# Shield_GRBL_V2.net
KiCad netlist of a schematic drawn in EAGLE
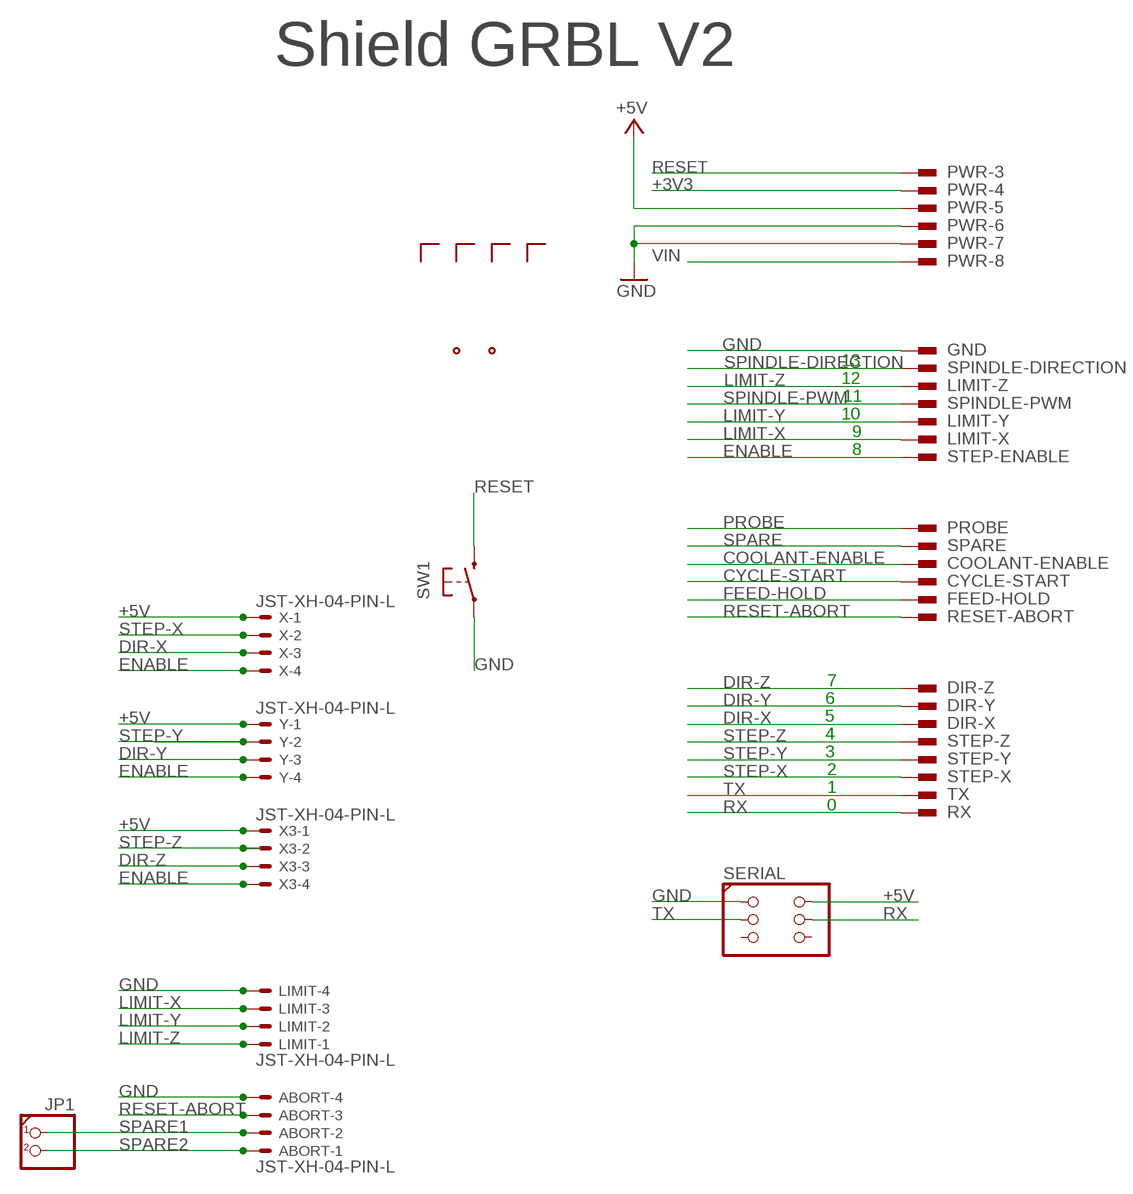
[diagram p0: schematic, sheet 1]

(export (version "E")
  (design (tool "Eeschema 10.0.6"))
  (components
    (comp (ref "ABORT")
      (value "JST-XH-04-PIN-L")
      (footprint "eagle-import:JST-XH-04-PACKAGE-LONG-PAD")
      (libsource (lib "eagle-import") (part "JST-XH-04-PIN-L"))
    )
    (comp (ref "COOLANT-ENABLE")
      (value "PINHD-1X1")
      (footprint "eagle-import:1X01")
      (fields (field (name "MF") "TYCO ELECTRONICS") (field (name "MPN") "62221-1"))
      (libsource (lib "eagle-import") (part "PINHD-1X1"))
    )
    (comp (ref "CYCLE-START")
      (value "PINHD-1X1")
      (footprint "eagle-import:1X01")
      (fields (field (name "MF") "TYCO ELECTRONICS") (field (name "MPN") "62221-1"))
      (libsource (lib "eagle-import") (part "PINHD-1X1"))
    )
    (comp (ref "DIR-X")
      (value "PINHD-1X1")
      (footprint "eagle-import:1X01")
      (fields (field (name "MF") "TYCO ELECTRONICS") (field (name "MPN") "62221-1"))
      (libsource (lib "eagle-import") (part "PINHD-1X1"))
    )
    (comp (ref "DIR-Y")
      (value "PINHD-1X1")
      (footprint "eagle-import:1X01")
      (fields (field (name "MF") "TYCO ELECTRONICS") (field (name "MPN") "62221-1"))
      (libsource (lib "eagle-import") (part "PINHD-1X1"))
    )
    (comp (ref "DIR-Z")
      (value "PINHD-1X1")
      (footprint "eagle-import:1X01")
      (fields (field (name "MF") "TYCO ELECTRONICS") (field (name "MPN") "62221-1"))
      (libsource (lib "eagle-import") (part "PINHD-1X1"))
    )
    (comp (ref "FEED-HOLD")
      (value "PINHD-1X1")
      (footprint "eagle-import:1X01")
      (fields (field (name "MF") "TYCO ELECTRONICS") (field (name "MPN") "62221-1"))
      (libsource (lib "eagle-import") (part "PINHD-1X1"))
    )
    (comp (ref "GND")
      (value "PINHD-1X1")
      (footprint "eagle-import:1X01")
      (fields (field (name "MF") "TYCO ELECTRONICS") (field (name "MPN") "62221-1"))
      (libsource (lib "eagle-import") (part "PINHD-1X1"))
    )
    (comp (ref "JP1")
      (value "PINHD-1X2")
      (footprint "eagle-import:1X02")
      (libsource (lib "eagle-import") (part "PINHD-1X2"))
    )
    (comp (ref "LIMIT")
      (value "JST-XH-04-PIN-L")
      (footprint "eagle-import:JST-XH-04-PACKAGE-LONG-PAD")
      (libsource (lib "eagle-import") (part "JST-XH-04-PIN-L"))
    )
    (comp (ref "LIMIT-X")
      (value "PINHD-1X1")
      (footprint "eagle-import:1X01")
      (fields (field (name "MF") "TYCO ELECTRONICS") (field (name "MPN") "62221-1"))
      (libsource (lib "eagle-import") (part "PINHD-1X1"))
    )
    (comp (ref "LIMIT-Y")
      (value "PINHD-1X1")
      (footprint "eagle-import:1X01")
      (fields (field (name "MF") "TYCO ELECTRONICS") (field (name "MPN") "62221-1"))
      (libsource (lib "eagle-import") (part "PINHD-1X1"))
    )
    (comp (ref "LIMIT-Z")
      (value "PINHD-1X1")
      (footprint "eagle-import:1X01")
      (fields (field (name "MF") "TYCO ELECTRONICS") (field (name "MPN") "62221-1"))
      (libsource (lib "eagle-import") (part "PINHD-1X1"))
    )
    (comp (ref "PROBE")
      (value "PINHD-1X1")
      (footprint "eagle-import:1X01")
      (fields (field (name "MF") "TYCO ELECTRONICS") (field (name "MPN") "62221-1"))
      (libsource (lib "eagle-import") (part "PINHD-1X1"))
    )
    (comp (ref "PWR-3")
      (value "PINHD-1X1")
      (footprint "eagle-import:1X01")
      (fields (field (name "MF") "TYCO ELECTRONICS") (field (name "MPN") "62221-1"))
      (libsource (lib "eagle-import") (part "PINHD-1X1"))
    )
    (comp (ref "PWR-4")
      (value "PINHD-1X1")
      (footprint "eagle-import:1X01")
      (fields (field (name "MF") "TYCO ELECTRONICS") (field (name "MPN") "62221-1"))
      (libsource (lib "eagle-import") (part "PINHD-1X1"))
    )
    (comp (ref "PWR-5")
      (value "PINHD-1X1")
      (footprint "eagle-import:1X01")
      (fields (field (name "MF") "TYCO ELECTRONICS") (field (name "MPN") "62221-1"))
      (libsource (lib "eagle-import") (part "PINHD-1X1"))
    )
    (comp (ref "PWR-6")
      (value "PINHD-1X1")
      (footprint "eagle-import:1X01")
      (fields (field (name "MF") "TYCO ELECTRONICS") (field (name "MPN") "62221-1"))
      (libsource (lib "eagle-import") (part "PINHD-1X1"))
    )
    (comp (ref "PWR-7")
      (value "PINHD-1X1")
      (footprint "eagle-import:1X01")
      (fields (field (name "MF") "TYCO ELECTRONICS") (field (name "MPN") "62221-1"))
      (libsource (lib "eagle-import") (part "PINHD-1X1"))
    )
    (comp (ref "PWR-8")
      (value "PINHD-1X1")
      (footprint "eagle-import:1X01")
      (fields (field (name "MF") "TYCO ELECTRONICS") (field (name "MPN") "62221-1"))
      (libsource (lib "eagle-import") (part "PINHD-1X1"))
    )
    (comp (ref "RESET-ABORT")
      (value "PINHD-1X1")
      (footprint "eagle-import:1X01")
      (fields (field (name "MF") "TYCO ELECTRONICS") (field (name "MPN") "62221-1"))
      (libsource (lib "eagle-import") (part "PINHD-1X1"))
    )
    (comp (ref "RX")
      (value "PINHD-1X1")
      (footprint "eagle-import:1X01")
      (fields (field (name "MF") "TYCO ELECTRONICS") (field (name "MPN") "62221-1"))
      (libsource (lib "eagle-import") (part "PINHD-1X1"))
    )
    (comp (ref "SERIAL")
      (value "3x2 M")
      (footprint "eagle-import:2X03S")
      (libsource (lib "eagle-import") (part "PINHD-2X3S"))
    )
    (comp (ref "SPARE")
      (value "PINHD-1X1")
      (footprint "eagle-import:1X01")
      (fields (field (name "MF") "TYCO ELECTRONICS") (field (name "MPN") "62221-1"))
      (libsource (lib "eagle-import") (part "PINHD-1X1"))
    )
    (comp (ref "SPINDLE-DIRECTION")
      (value "PINHD-1X1")
      (footprint "eagle-import:1X01")
      (fields (field (name "MF") "TYCO ELECTRONICS") (field (name "MPN") "62221-1"))
      (libsource (lib "eagle-import") (part "PINHD-1X1"))
    )
    (comp (ref "SPINDLE-PWM")
      (value "PINHD-1X1")
      (footprint "eagle-import:1X01")
      (fields (field (name "MF") "TYCO ELECTRONICS") (field (name "MPN") "62221-1"))
      (libsource (lib "eagle-import") (part "PINHD-1X1"))
    )
    (comp (ref "STEP-ENABLE")
      (value "PINHD-1X1")
      (footprint "eagle-import:1X01")
      (fields (field (name "MF") "TYCO ELECTRONICS") (field (name "MPN") "62221-1"))
      (libsource (lib "eagle-import") (part "PINHD-1X1"))
    )
    (comp (ref "STEP-X")
      (value "PINHD-1X1")
      (footprint "eagle-import:1X01")
      (fields (field (name "MF") "TYCO ELECTRONICS") (field (name "MPN") "62221-1"))
      (libsource (lib "eagle-import") (part "PINHD-1X1"))
    )
    (comp (ref "STEP-Y")
      (value "PINHD-1X1")
      (footprint "eagle-import:1X01")
      (fields (field (name "MF") "TYCO ELECTRONICS") (field (name "MPN") "62221-1"))
      (libsource (lib "eagle-import") (part "PINHD-1X1"))
    )
    (comp (ref "STEP-Z")
      (value "PINHD-1X1")
      (footprint "eagle-import:1X01")
      (fields (field (name "MF") "TYCO ELECTRONICS") (field (name "MPN") "62221-1"))
      (libsource (lib "eagle-import") (part "PINHD-1X1"))
    )
    (comp (ref "SW1")
      (value "SWITCH1X2")
      (footprint "eagle-import:SW8X4-SMD")
      (libsource (lib "eagle-import") (part "SWITCH1X2"))
    )
    (comp (ref "TX")
      (value "PINHD-1X1")
      (footprint "eagle-import:1X01")
      (fields (field (name "MF") "TYCO ELECTRONICS") (field (name "MPN") "62221-1"))
      (libsource (lib "eagle-import") (part "PINHD-1X1"))
    )
    (comp (ref "U$1")
      (value "MARKERDUAL-60")
      (footprint "eagle-import:MARKER60")
      (libsource (lib "eagle-import") (part "MARKERDUAL-60"))
    )
    (comp (ref "U$2")
      (value "MARKER")
      (footprint "eagle-import:MARKER")
      (libsource (lib "eagle-import") (part "MARKER"))
    )
    (comp (ref "U$3")
      (value "MARKER")
      (footprint "eagle-import:MARKER")
      (libsource (lib "eagle-import") (part "MARKER"))
    )
    (comp (ref "U$4")
      (value "MARKER")
      (footprint "eagle-import:MARKER")
      (libsource (lib "eagle-import") (part "MARKER"))
    )
    (comp (ref "U$5")
      (value "MARKER")
      (footprint "eagle-import:MARKER")
      (libsource (lib "eagle-import") (part "MARKER"))
    )
    (comp (ref "X")
      (value "JST-XH-04-PIN-L")
      (footprint "eagle-import:JST-XH-04-PACKAGE-LONG-PAD")
      (libsource (lib "eagle-import") (part "JST-XH-04-PIN-L"))
    )
    (comp (ref "X3")
      (value "JST-XH-04-PIN-L")
      (footprint "eagle-import:JST-XH-04-PACKAGE-LONG-PAD")
      (libsource (lib "eagle-import") (part "JST-XH-04-PIN-L"))
    )
    (comp (ref "Y")
      (value "JST-XH-04-PIN-L")
      (footprint "eagle-import:JST-XH-04-PACKAGE-LONG-PAD")
      (libsource (lib "eagle-import") (part "JST-XH-04-PIN-L"))
    )
  )
  (nets
    (net (code "1") (name "+5V") (class "Default")
      (node (ref "PWR-5") (pin "1") (pinfunction "1_1") (pintype "passive"))
      (node (ref "SERIAL") (pin "2") (pinfunction "2_2") (pintype "passive"))
      (node (ref "X") (pin "1") (pinfunction "S_1") (pintype "passive"))
      (node (ref "X3") (pin "1") (pinfunction "S_1") (pintype "passive"))
      (node (ref "Y") (pin "1") (pinfunction "S_1") (pintype "passive"))
    )
    (net (code "2") (name "/+3V3") (class "Default")
      (node (ref "PWR-4") (pin "1") (pinfunction "1_1") (pintype "passive"))
    )
    (net (code "3") (name "/COOLANT-ENABLE") (class "Default")
      (node (ref "COOLANT-ENABLE") (pin "1") (pinfunction "1_1") (pintype "passive"))
    )
    (net (code "4") (name "/CYCLE-START") (class "Default")
      (node (ref "CYCLE-START") (pin "1") (pinfunction "1_1") (pintype "passive"))
    )
    (net (code "5") (name "/DIR-X") (class "Default")
      (node (ref "DIR-X") (pin "1") (pinfunction "1_1") (pintype "passive"))
      (node (ref "X") (pin "3") (pinfunction "S_3") (pintype "passive"))
    )
    (net (code "6") (name "/DIR-Y") (class "Default")
      (node (ref "DIR-Y") (pin "1") (pinfunction "1_1") (pintype "passive"))
      (node (ref "Y") (pin "3") (pinfunction "S_3") (pintype "passive"))
    )
    (net (code "7") (name "/DIR-Z") (class "Default")
      (node (ref "DIR-Z") (pin "1") (pinfunction "1_1") (pintype "passive"))
      (node (ref "X3") (pin "3") (pinfunction "S_3") (pintype "passive"))
    )
    (net (code "8") (name "/ENABLE") (class "Default")
      (node (ref "STEP-ENABLE") (pin "1") (pinfunction "1_1") (pintype "passive"))
      (node (ref "X") (pin "4") (pinfunction "S_4") (pintype "passive"))
      (node (ref "X3") (pin "4") (pinfunction "S_4") (pintype "passive"))
      (node (ref "Y") (pin "4") (pinfunction "S_4") (pintype "passive"))
    )
    (net (code "9") (name "/FEED-HOLD") (class "Default")
      (node (ref "FEED-HOLD") (pin "1") (pinfunction "1_1") (pintype "passive"))
    )
    (net (code "10") (name "/LIMIT-X") (class "Default")
      (node (ref "LIMIT") (pin "3") (pinfunction "S_3") (pintype "passive"))
      (node (ref "LIMIT-X") (pin "1") (pinfunction "1_1") (pintype "passive"))
    )
    (net (code "11") (name "/LIMIT-Y") (class "Default")
      (node (ref "LIMIT") (pin "2") (pinfunction "S_2") (pintype "passive"))
      (node (ref "LIMIT-Y") (pin "1") (pinfunction "1_1") (pintype "passive"))
    )
    (net (code "12") (name "/LIMIT-Z") (class "Default")
      (node (ref "LIMIT") (pin "1") (pinfunction "S_1") (pintype "passive"))
      (node (ref "LIMIT-Z") (pin "1") (pinfunction "1_1") (pintype "passive"))
    )
    (net (code "13") (name "/PROBE") (class "Default")
      (node (ref "PROBE") (pin "1") (pinfunction "1_1") (pintype "passive"))
    )
    (net (code "14") (name "/RESET") (class "Default")
      (node (ref "PWR-3") (pin "1") (pinfunction "1_1") (pintype "passive"))
      (node (ref "SW1") (pin "2") (pinfunction "S_2") (pintype "passive"))
    )
    (net (code "15") (name "/RESET-ABORT") (class "Default")
      (node (ref "ABORT") (pin "3") (pinfunction "S_3") (pintype "passive"))
      (node (ref "RESET-ABORT") (pin "1") (pinfunction "1_1") (pintype "passive"))
    )
    (net (code "16") (name "/RX") (class "Default")
      (node (ref "RX") (pin "1") (pinfunction "1_1") (pintype "passive"))
      (node (ref "SERIAL") (pin "4") (pinfunction "4_4") (pintype "passive"))
    )
    (net (code "17") (name "/SPARE") (class "Default")
      (node (ref "SPARE") (pin "1") (pinfunction "1_1") (pintype "passive"))
    )
    (net (code "18") (name "/SPARE1") (class "Default")
      (node (ref "ABORT") (pin "2") (pinfunction "S_2") (pintype "passive"))
      (node (ref "JP1") (pin "1") (pinfunction "1_1") (pintype "passive"))
    )
    (net (code "19") (name "/SPARE2") (class "Default")
      (node (ref "ABORT") (pin "1") (pinfunction "S_1") (pintype "passive"))
      (node (ref "JP1") (pin "2") (pinfunction "2_2") (pintype "passive"))
    )
    (net (code "20") (name "/SPINDLE-DIRECTION") (class "Default")
      (node (ref "SPINDLE-DIRECTION") (pin "1") (pinfunction "1_1") (pintype "passive"))
    )
    (net (code "21") (name "/SPINDLE-PWM") (class "Default")
      (node (ref "SPINDLE-PWM") (pin "1") (pinfunction "1_1") (pintype "passive"))
    )
    (net (code "22") (name "/STEP-X") (class "Default")
      (node (ref "STEP-X") (pin "1") (pinfunction "1_1") (pintype "passive"))
      (node (ref "X") (pin "2") (pinfunction "S_2") (pintype "passive"))
    )
    (net (code "23") (name "/STEP-Y") (class "Default")
      (node (ref "STEP-Y") (pin "1") (pinfunction "1_1") (pintype "passive"))
      (node (ref "Y") (pin "2") (pinfunction "S_2") (pintype "passive"))
    )
    (net (code "24") (name "/STEP-Z") (class "Default")
      (node (ref "STEP-Z") (pin "1") (pinfunction "1_1") (pintype "passive"))
      (node (ref "X3") (pin "2") (pinfunction "S_2") (pintype "passive"))
    )
    (net (code "25") (name "/TX") (class "Default")
      (node (ref "SERIAL") (pin "3") (pinfunction "3_3") (pintype "passive"))
      (node (ref "TX") (pin "1") (pinfunction "1_1") (pintype "passive"))
    )
    (net (code "26") (name "/VIN") (class "Default")
      (node (ref "PWR-8") (pin "1") (pinfunction "1_1") (pintype "passive"))
    )
    (net (code "27") (name "GND") (class "Default")
      (node (ref "ABORT") (pin "4") (pinfunction "S_4") (pintype "passive"))
      (node (ref "GND") (pin "1") (pinfunction "1_1") (pintype "passive"))
      (node (ref "LIMIT") (pin "4") (pinfunction "S_4") (pintype "passive"))
      (node (ref "PWR-6") (pin "1") (pinfunction "1_1") (pintype "passive"))
      (node (ref "PWR-7") (pin "1") (pinfunction "1_1") (pintype "passive"))
      (node (ref "SERIAL") (pin "1") (pinfunction "1_1") (pintype "passive"))
      (node (ref "SW1") (pin "1") (pinfunction "P_1") (pintype "passive"))
    )
    (net (code "28") (name "unconnected-(SERIAL-Pad5)") (class "Default")
      (node (ref "SERIAL") (pin "5") (pinfunction "5_5") (pintype "passive"))
    )
    (net (code "29") (name "unconnected-(SERIAL-Pad6)") (class "Default")
      (node (ref "SERIAL") (pin "6") (pinfunction "6_6") (pintype "passive"))
    )
  )
)
